# Pressure_Taps_CAN.net
KiCad netlist of a schematic drawn in Altium Designer
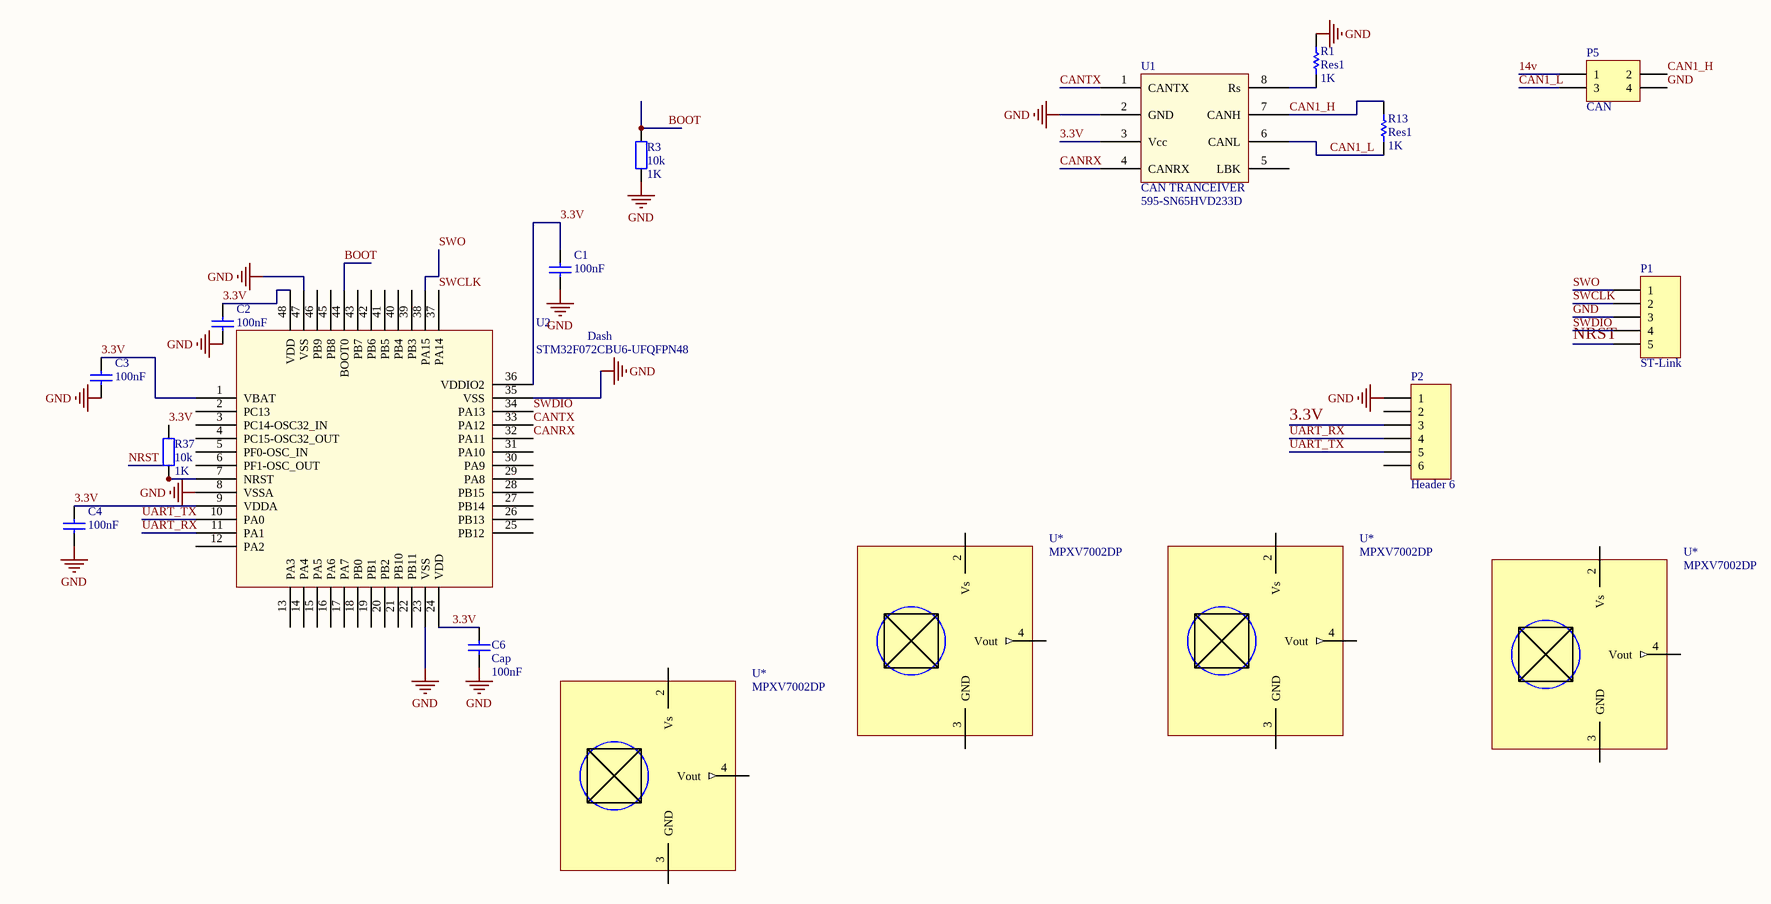
[diagram p0: Pressure Taps CAN.SchDoc]

(export (version "E")
  (design (tool "Eeschema 10.0.6"))
  (components
    (comp (ref "C1")
      (value "100nF")
      (footprint "R0805")
      (description "Capacitor (Semiconductor SIM Model)")
      (fields (field (name "PUBLISHER") "Altium Limited"))
      (libsource (lib "Miscellaneous Devices") (part "Cap Semi"))
    )
    (comp (ref "C2")
      (value "100nF")
      (footprint "R0805")
      (description "Capacitor (Semiconductor SIM Model)")
      (fields (field (name "PUBLISHER") "Altium Limited"))
      (libsource (lib "Miscellaneous Devices") (part "Cap Semi"))
    )
    (comp (ref "C3")
      (value "100nF")
      (footprint "R0805")
      (description "Capacitor (Semiconductor SIM Model)")
      (fields (field (name "PUBLISHER") "Altium Limited"))
      (libsource (lib "Miscellaneous Devices") (part "Cap Semi"))
    )
    (comp (ref "C4")
      (value "100nF")
      (footprint "R0805")
      (description "Capacitor (Semiconductor SIM Model)")
      (fields (field (name "PUBLISHER") "Altium Limited"))
      (libsource (lib "Miscellaneous Devices") (part "Cap Semi"))
    )
    (comp (ref "C6")
      (value "Cap")
      (footprint "R0805")
      (description "Capacitor")
      (fields (field (name "ALTIUM_VALUE") "100nF") (field (name "PUBLISHER") "Altium Limited"))
      (libsource (lib "Miscellaneous Devices") (part "Cap"))
    )
    (comp (ref "P1")
      (value "ST-Link")
      (footprint "SMD 5Wire - Small")
      (description "Header, 5-Pin")
      (fields (field (name "PUBLISHER") "Altium Limited"))
      (libsource (lib "Miscellaneous Connectors") (part "Header 5"))
    )
    (comp (ref "P2")
      (value "Header 6")
      (footprint "HDR1X6")
      (description "Header, 6-Pin")
      (fields (field (name "PUBLISHER") "Altium Limited"))
      (libsource (lib "Miscellaneous Connectors") (part "Header 6"))
    )
    (comp (ref "P5")
      (value "CAN")
      (footprint "SMD 4Wire")
      (description "Header, 2-Pin, Dual row, Right Angle")
      (fields (field (name "PUBLISHER") "Altium Limited"))
      (libsource (lib "Miscellaneous Connectors") (part "Header 2X2H"))
    )
    (comp (ref "R1")
      (value "Res1")
      (footprint "R0805")
      (description "Resistor")
      (fields (field (name "ALTIUM_VALUE") "1K") (field (name "PUBLISHER") "Altium Limited"))
      (libsource (lib "Miscellaneous Devices") (part "Res1"))
    )
    (comp (ref "R3")
      (value "10k")
      (footprint "R0805")
      (description "Resistor")
      (fields (field (name "ALTIUM_VALUE") "1K") (field (name "PUBLISHER") "Altium Limited"))
      (libsource (lib "Miscellaneous Devices") (part "Res2"))
    )
    (comp (ref "R13")
      (value "Res1")
      (footprint "R0805")
      (description "Resistor")
      (fields (field (name "ALTIUM_VALUE") "1K") (field (name "PUBLISHER") "Altium Limited"))
      (libsource (lib "Miscellaneous Devices") (part "Res1"))
    )
    (comp (ref "R37")
      (value "10k")
      (footprint "R0805")
      (description "Resistor")
      (fields (field (name "ALTIUM_VALUE") "1K") (field (name "PUBLISHER") "Altium Limited"))
      (libsource (lib "Miscellaneous Devices") (part "Res2"))
    )
    (comp (ref "U*")
      (value "MPXV7002DP")
      (footprint "MPXV7002DP")
      (description "Freescale MPXV7002DP 2 kPa Differential Pressure Sensor")
      (libsource (lib "Misc_ICs-1") (part "MPXV7002DP"))
    )
    (comp (ref "U1")
      (value "CAN TRANCEIVER")
      (footprint "SOP8")
      (fields (field (name "SUPPLIER PART NUMBER 1") "595-SN65HVD233D"))
      (libsource (lib "Misc_ICs-1") (part "595-SN65HVD233"))
    )
    (comp (ref "U2")
      (value "Dash")
      (footprint "STM32F072CBU6 - No Heatsink")
      (description "PDM Mk21 MICRO")
      (fields
        (field (name "MANUFACTURER") "ST Microelectrics")
        (field (name "PART NUMBER") "STM32F072CBU6-UFQFPN48")
      )
      (libsource (lib "STM32_1") (part "STM32F072CBU6"))
    )
  )
  (nets
    (net (code "1") (name "/3.3V") (class "Default")
      (node (ref "C1") (pin "2") (pinfunction "2_2") (pintype "passive"))
      (node (ref "C2") (pin "2") (pinfunction "2_2") (pintype "passive"))
      (node (ref "C3") (pin "2") (pinfunction "2_2") (pintype "passive"))
      (node (ref "C4") (pin "2") (pinfunction "2_2") (pintype "passive"))
      (node (ref "C6") (pin "1") (pinfunction "1_1") (pintype "passive"))
      (node (ref "P2") (pin "3") (pinfunction "3_3") (pintype "passive"))
      (node (ref "R37") (pin "2") (pinfunction "2_2") (pintype "passive"))
      (node (ref "U1") (pin "3") (pinfunction "Vcc_3") (pintype "passive"))
      (node (ref "U2") (pin "1") (pinfunction "VBAT_1") (pintype "passive"))
      (node (ref "U2") (pin "24") (pinfunction "VDD_24") (pintype "passive"))
      (node (ref "U2") (pin "36") (pinfunction "VDDIO2_36") (pintype "passive"))
      (node (ref "U2") (pin "48") (pinfunction "VDD_48") (pintype "passive"))
      (node (ref "U2") (pin "9") (pinfunction "VDDA_9") (pintype "passive"))
    )
    (net (code "2") (name "/14v") (class "Default")
      (node (ref "P5") (pin "1") (pinfunction "1_1") (pintype "passive"))
    )
    (net (code "3") (name "/BOOT") (class "Default")
      (node (ref "R3") (pin "2") (pinfunction "2_2") (pintype "passive"))
      (node (ref "U2") (pin "44") (pinfunction "BOOT0_44") (pintype "passive"))
    )
    (net (code "4") (name "/CAN1_H") (class "Default")
      (node (ref "P5") (pin "2") (pinfunction "2_2") (pintype "passive"))
      (node (ref "R13") (pin "2") (pinfunction "2_2") (pintype "passive"))
      (node (ref "U1") (pin "7") (pinfunction "CANH_7") (pintype "passive"))
    )
    (net (code "5") (name "/CAN1_L") (class "Default")
      (node (ref "P5") (pin "3") (pinfunction "3_3") (pintype "passive"))
      (node (ref "R13") (pin "1") (pinfunction "1_1") (pintype "passive"))
      (node (ref "U1") (pin "6") (pinfunction "CANL_6") (pintype "passive"))
    )
    (net (code "6") (name "/CANRX") (class "Default")
      (node (ref "U1") (pin "4") (pinfunction "CANRX_4") (pintype "passive"))
      (node (ref "U2") (pin "32") (pinfunction "PA11_32") (pintype "passive"))
    )
    (net (code "7") (name "/CANTX") (class "Default")
      (node (ref "U1") (pin "1") (pinfunction "CANTX_1") (pintype "passive"))
      (node (ref "U2") (pin "33") (pinfunction "PA12_33") (pintype "passive"))
    )
    (net (code "8") (name "/NRST") (class "Default")
      (node (ref "P1") (pin "5") (pinfunction "5_5") (pintype "passive"))
      (node (ref "R37") (pin "1") (pinfunction "1_1") (pintype "passive"))
      (node (ref "U2") (pin "7") (pinfunction "NRST_7") (pintype "passive"))
    )
    (net (code "9") (name "/SWCLK") (class "Default")
      (node (ref "P1") (pin "2") (pinfunction "2_2") (pintype "passive"))
      (node (ref "U2") (pin "37") (pinfunction "PA14_37") (pintype "passive"))
    )
    (net (code "10") (name "/SWDIO") (class "Default")
      (node (ref "P1") (pin "4") (pinfunction "4_4") (pintype "passive"))
      (node (ref "U2") (pin "34") (pinfunction "PA13_34") (pintype "passive"))
    )
    (net (code "11") (name "/SWO") (class "Default")
      (node (ref "P1") (pin "1") (pinfunction "1_1") (pintype "passive"))
      (node (ref "U2") (pin "38") (pinfunction "PA15_38") (pintype "passive"))
    )
    (net (code "12") (name "/UART_RX") (class "Default")
      (node (ref "P2") (pin "4") (pinfunction "4_4") (pintype "passive"))
      (node (ref "U2") (pin "11") (pinfunction "PA1_11") (pintype "passive"))
    )
    (net (code "13") (name "/UART_TX") (class "Default")
      (node (ref "P2") (pin "5") (pinfunction "5_5") (pintype "passive"))
      (node (ref "U2") (pin "10") (pinfunction "PA0_10") (pintype "passive"))
    )
    (net (code "14") (name "GND") (class "Default")
      (node (ref "C1") (pin "1") (pinfunction "1_1") (pintype "passive"))
      (node (ref "C2") (pin "1") (pinfunction "1_1") (pintype "passive"))
      (node (ref "C3") (pin "1") (pinfunction "1_1") (pintype "passive"))
      (node (ref "C4") (pin "1") (pinfunction "1_1") (pintype "passive"))
      (node (ref "C6") (pin "2") (pinfunction "2_2") (pintype "passive"))
      (node (ref "P1") (pin "3") (pinfunction "3_3") (pintype "passive"))
      (node (ref "P2") (pin "1") (pinfunction "1_1") (pintype "passive"))
      (node (ref "P5") (pin "4") (pinfunction "4_4") (pintype "passive"))
      (node (ref "R1") (pin "2") (pinfunction "2_2") (pintype "passive"))
      (node (ref "R3") (pin "1") (pinfunction "1_1") (pintype "passive"))
      (node (ref "U1") (pin "2") (pinfunction "GND_2") (pintype "passive"))
      (node (ref "U2") (pin "23") (pinfunction "VSS_23") (pintype "passive"))
      (node (ref "U2") (pin "35") (pinfunction "VSS_35") (pintype "passive"))
      (node (ref "U2") (pin "47") (pinfunction "VSS_47") (pintype "passive"))
      (node (ref "U2") (pin "8") (pinfunction "VSSA_8") (pintype "passive"))
    )
    (net (code "15") (name "Net-(U1-Rs)") (class "Default")
      (node (ref "R1") (pin "1") (pinfunction "1_1") (pintype "passive"))
      (node (ref "U1") (pin "8") (pinfunction "Rs_8") (pintype "passive"))
    )
    (net (code "16") (name "unconnected-(P2-Pad2)") (class "Default")
      (node (ref "P2") (pin "2") (pinfunction "2_2") (pintype "passive"))
    )
    (net (code "17") (name "unconnected-(P2-Pad6)") (class "Default")
      (node (ref "P2") (pin "6") (pinfunction "6_6") (pintype "passive"))
    )
    (net (code "18") (name "unconnected-(U*-GND-Pad3)") (class "Default")
      (node (ref "U*") (pin "3") (pinfunction "GND_3") (pintype "power_in"))
    )
    (net (code "19") (name "unconnected-(U*-GND-Pad3)_1") (class "Default")
      (node (ref "U*") (pin "3") (pinfunction "GND_3") (pintype "power_in"))
    )
    (net (code "20") (name "unconnected-(U*-GND-Pad3)_2") (class "Default")
      (node (ref "U*") (pin "3") (pinfunction "GND_3") (pintype "power_in"))
    )
    (net (code "21") (name "unconnected-(U*-GND-Pad3)_3") (class "Default")
      (node (ref "U*") (pin "3") (pinfunction "GND_3") (pintype "power_in"))
    )
    (net (code "22") (name "unconnected-(U*-NC-Pad1)") (class "Default")
      (node (ref "U*") (pin "1") (pinfunction "NC_1") (pintype "passive"))
    )
    (net (code "23") (name "unconnected-(U*-NC-Pad1)_1") (class "Default")
      (node (ref "U*") (pin "1") (pinfunction "NC_1") (pintype "passive"))
    )
    (net (code "24") (name "unconnected-(U*-NC-Pad1)_2") (class "Default")
      (node (ref "U*") (pin "1") (pinfunction "NC_1") (pintype "passive"))
    )
    (net (code "25") (name "unconnected-(U*-NC-Pad1)_3") (class "Default")
      (node (ref "U*") (pin "1") (pinfunction "NC_1") (pintype "passive"))
    )
    (net (code "26") (name "unconnected-(U*-NC-Pad5)") (class "Default")
      (node (ref "U*") (pin "5") (pinfunction "NC_5") (pintype "passive"))
    )
    (net (code "27") (name "unconnected-(U*-NC-Pad5)_1") (class "Default")
      (node (ref "U*") (pin "5") (pinfunction "NC_5") (pintype "passive"))
    )
    (net (code "28") (name "unconnected-(U*-NC-Pad5)_2") (class "Default")
      (node (ref "U*") (pin "5") (pinfunction "NC_5") (pintype "passive"))
    )
    (net (code "29") (name "unconnected-(U*-NC-Pad5)_3") (class "Default")
      (node (ref "U*") (pin "5") (pinfunction "NC_5") (pintype "passive"))
    )
    (net (code "30") (name "unconnected-(U*-NC-Pad6)") (class "Default")
      (node (ref "U*") (pin "6") (pinfunction "NC_6") (pintype "passive"))
    )
    (net (code "31") (name "unconnected-(U*-NC-Pad6)_1") (class "Default")
      (node (ref "U*") (pin "6") (pinfunction "NC_6") (pintype "passive"))
    )
    (net (code "32") (name "unconnected-(U*-NC-Pad6)_2") (class "Default")
      (node (ref "U*") (pin "6") (pinfunction "NC_6") (pintype "passive"))
    )
    (net (code "33") (name "unconnected-(U*-NC-Pad6)_3") (class "Default")
      (node (ref "U*") (pin "6") (pinfunction "NC_6") (pintype "passive"))
    )
    (net (code "34") (name "unconnected-(U*-NC-Pad8)") (class "Default")
      (node (ref "U*") (pin "8") (pinfunction "NC_8") (pintype "passive"))
    )
    (net (code "35") (name "unconnected-(U*-NC-Pad8)_1") (class "Default")
      (node (ref "U*") (pin "8") (pinfunction "NC_8") (pintype "passive"))
    )
    (net (code "36") (name "unconnected-(U*-NC-Pad8)_2") (class "Default")
      (node (ref "U*") (pin "8") (pinfunction "NC_8") (pintype "passive"))
    )
    (net (code "37") (name "unconnected-(U*-NC-Pad8)_3") (class "Default")
      (node (ref "U*") (pin "8") (pinfunction "NC_8") (pintype "passive"))
    )
    (net (code "38") (name "unconnected-(U*-NC-PadN)") (class "Default")
      (node (ref "U*") (pin "N") (pinfunction "NC_N") (pintype "passive"))
    )
    (net (code "39") (name "unconnected-(U*-NC-PadN)_1") (class "Default")
      (node (ref "U*") (pin "N") (pinfunction "NC_N") (pintype "passive"))
    )
    (net (code "40") (name "unconnected-(U*-NC-PadN)_2") (class "Default")
      (node (ref "U*") (pin "N") (pinfunction "NC_N") (pintype "passive"))
    )
    (net (code "41") (name "unconnected-(U*-NC-PadN)_3") (class "Default")
      (node (ref "U*") (pin "N") (pinfunction "NC_N") (pintype "passive"))
    )
    (net (code "42") (name "unconnected-(U*-Vout-Pad4)") (class "Default")
      (node (ref "U*") (pin "4") (pinfunction "Vout_4") (pintype "output"))
    )
    (net (code "43") (name "unconnected-(U*-Vout-Pad4)_1") (class "Default")
      (node (ref "U*") (pin "4") (pinfunction "Vout_4") (pintype "output"))
    )
    (net (code "44") (name "unconnected-(U*-Vout-Pad4)_2") (class "Default")
      (node (ref "U*") (pin "4") (pinfunction "Vout_4") (pintype "output"))
    )
    (net (code "45") (name "unconnected-(U*-Vout-Pad4)_3") (class "Default")
      (node (ref "U*") (pin "4") (pinfunction "Vout_4") (pintype "output"))
    )
    (net (code "46") (name "unconnected-(U*-Vs-Pad2)") (class "Default")
      (node (ref "U*") (pin "2") (pinfunction "Vs_2") (pintype "power_in"))
    )
    (net (code "47") (name "unconnected-(U*-Vs-Pad2)_1") (class "Default")
      (node (ref "U*") (pin "2") (pinfunction "Vs_2") (pintype "power_in"))
    )
    (net (code "48") (name "unconnected-(U*-Vs-Pad2)_2") (class "Default")
      (node (ref "U*") (pin "2") (pinfunction "Vs_2") (pintype "power_in"))
    )
    (net (code "49") (name "unconnected-(U*-Vs-Pad2)_3") (class "Default")
      (node (ref "U*") (pin "2") (pinfunction "Vs_2") (pintype "power_in"))
    )
    (net (code "50") (name "unconnected-(U1-LBK-Pad5)") (class "Default")
      (node (ref "U1") (pin "5") (pinfunction "LBK_5") (pintype "passive"))
    )
    (net (code "51") (name "unconnected-(U2-PA2-Pad12)") (class "Default")
      (node (ref "U2") (pin "12") (pinfunction "PA2_12") (pintype "passive"))
    )
    (net (code "52") (name "unconnected-(U2-PA3-Pad13)") (class "Default")
      (node (ref "U2") (pin "13") (pinfunction "PA3_13") (pintype "passive"))
    )
    (net (code "53") (name "unconnected-(U2-PA4-Pad14)") (class "Default")
      (node (ref "U2") (pin "14") (pinfunction "PA4_14") (pintype "passive"))
    )
    (net (code "54") (name "unconnected-(U2-PA5-Pad15)") (class "Default")
      (node (ref "U2") (pin "15") (pinfunction "PA5_15") (pintype "passive"))
    )
    (net (code "55") (name "unconnected-(U2-PA6-Pad16)") (class "Default")
      (node (ref "U2") (pin "16") (pinfunction "PA6_16") (pintype "passive"))
    )
    (net (code "56") (name "unconnected-(U2-PA7-Pad17)") (class "Default")
      (node (ref "U2") (pin "17") (pinfunction "PA7_17") (pintype "passive"))
    )
    (net (code "57") (name "unconnected-(U2-PA8-Pad29)") (class "Default")
      (node (ref "U2") (pin "29") (pinfunction "PA8_29") (pintype "passive"))
    )
    (net (code "58") (name "unconnected-(U2-PA9-Pad30)") (class "Default")
      (node (ref "U2") (pin "30") (pinfunction "PA9_30") (pintype "passive"))
    )
    (net (code "59") (name "unconnected-(U2-PA10-Pad31)") (class "Default")
      (node (ref "U2") (pin "31") (pinfunction "PA10_31") (pintype "passive"))
    )
    (net (code "60") (name "unconnected-(U2-PB0-Pad18)") (class "Default")
      (node (ref "U2") (pin "18") (pinfunction "PB0_18") (pintype "passive"))
    )
    (net (code "61") (name "unconnected-(U2-PB1-Pad19)") (class "Default")
      (node (ref "U2") (pin "19") (pinfunction "PB1_19") (pintype "passive"))
    )
    (net (code "62") (name "unconnected-(U2-PB2-Pad20)") (class "Default")
      (node (ref "U2") (pin "20") (pinfunction "PB2_20") (pintype "passive"))
    )
    (net (code "63") (name "unconnected-(U2-PB3-Pad39)") (class "Default")
      (node (ref "U2") (pin "39") (pinfunction "PB3_39") (pintype "passive"))
    )
    (net (code "64") (name "unconnected-(U2-PB4-Pad40)") (class "Default")
      (node (ref "U2") (pin "40") (pinfunction "PB4_40") (pintype "passive"))
    )
    (net (code "65") (name "unconnected-(U2-PB5-Pad41)") (class "Default")
      (node (ref "U2") (pin "41") (pinfunction "PB5_41") (pintype "passive"))
    )
    (net (code "66") (name "unconnected-(U2-PB6-Pad42)") (class "Default")
      (node (ref "U2") (pin "42") (pinfunction "PB6_42") (pintype "passive"))
    )
    (net (code "67") (name "unconnected-(U2-PB7-Pad43)") (class "Default")
      (node (ref "U2") (pin "43") (pinfunction "PB7_43") (pintype "passive"))
    )
    (net (code "68") (name "unconnected-(U2-PB8-Pad45)") (class "Default")
      (node (ref "U2") (pin "45") (pinfunction "PB8_45") (pintype "passive"))
    )
    (net (code "69") (name "unconnected-(U2-PB9-Pad46)") (class "Default")
      (node (ref "U2") (pin "46") (pinfunction "PB9_46") (pintype "passive"))
    )
    (net (code "70") (name "unconnected-(U2-PB10-Pad21)") (class "Default")
      (node (ref "U2") (pin "21") (pinfunction "PB10_21") (pintype "passive"))
    )
    (net (code "71") (name "unconnected-(U2-PB11-Pad22)") (class "Default")
      (node (ref "U2") (pin "22") (pinfunction "PB11_22") (pintype "passive"))
    )
    (net (code "72") (name "unconnected-(U2-PB12-Pad25)") (class "Default")
      (node (ref "U2") (pin "25") (pinfunction "PB12_25") (pintype "passive"))
    )
    (net (code "73") (name "unconnected-(U2-PB13-Pad26)") (class "Default")
      (node (ref "U2") (pin "26") (pinfunction "PB13_26") (pintype "passive"))
    )
    (net (code "74") (name "unconnected-(U2-PB14-Pad27)") (class "Default")
      (node (ref "U2") (pin "27") (pinfunction "PB14_27") (pintype "passive"))
    )
    (net (code "75") (name "unconnected-(U2-PB15-Pad28)") (class "Default")
      (node (ref "U2") (pin "28") (pinfunction "PB15_28") (pintype "passive"))
    )
    (net (code "76") (name "unconnected-(U2-PC13-Pad2)") (class "Default")
      (node (ref "U2") (pin "2") (pinfunction "PC13_2") (pintype "passive"))
    )
    (net (code "77") (name "unconnected-(U2-PC14-OSC32_IN-Pad3)") (class "Default")
      (node (ref "U2") (pin "3") (pinfunction "PC14-OSC32_IN_3") (pintype "passive"))
    )
    (net (code "78") (name "unconnected-(U2-PC15-OSC32_OUT-Pad4)") (class "Default")
      (node (ref "U2") (pin "4") (pinfunction "PC15-OSC32_OUT_4") (pintype "passive"))
    )
    (net (code "79") (name "unconnected-(U2-PF0-OSC_IN-Pad5)") (class "Default")
      (node (ref "U2") (pin "5") (pinfunction "PF0-OSC_IN_5") (pintype "passive"))
    )
    (net (code "80") (name "unconnected-(U2-PF1-OSC_OUT-Pad6)") (class "Default")
      (node (ref "U2") (pin "6") (pinfunction "PF1-OSC_OUT_6") (pintype "passive"))
    )
  )
)
